# untitled.net
KiCad netlist of a schematic drawn in EAGLE
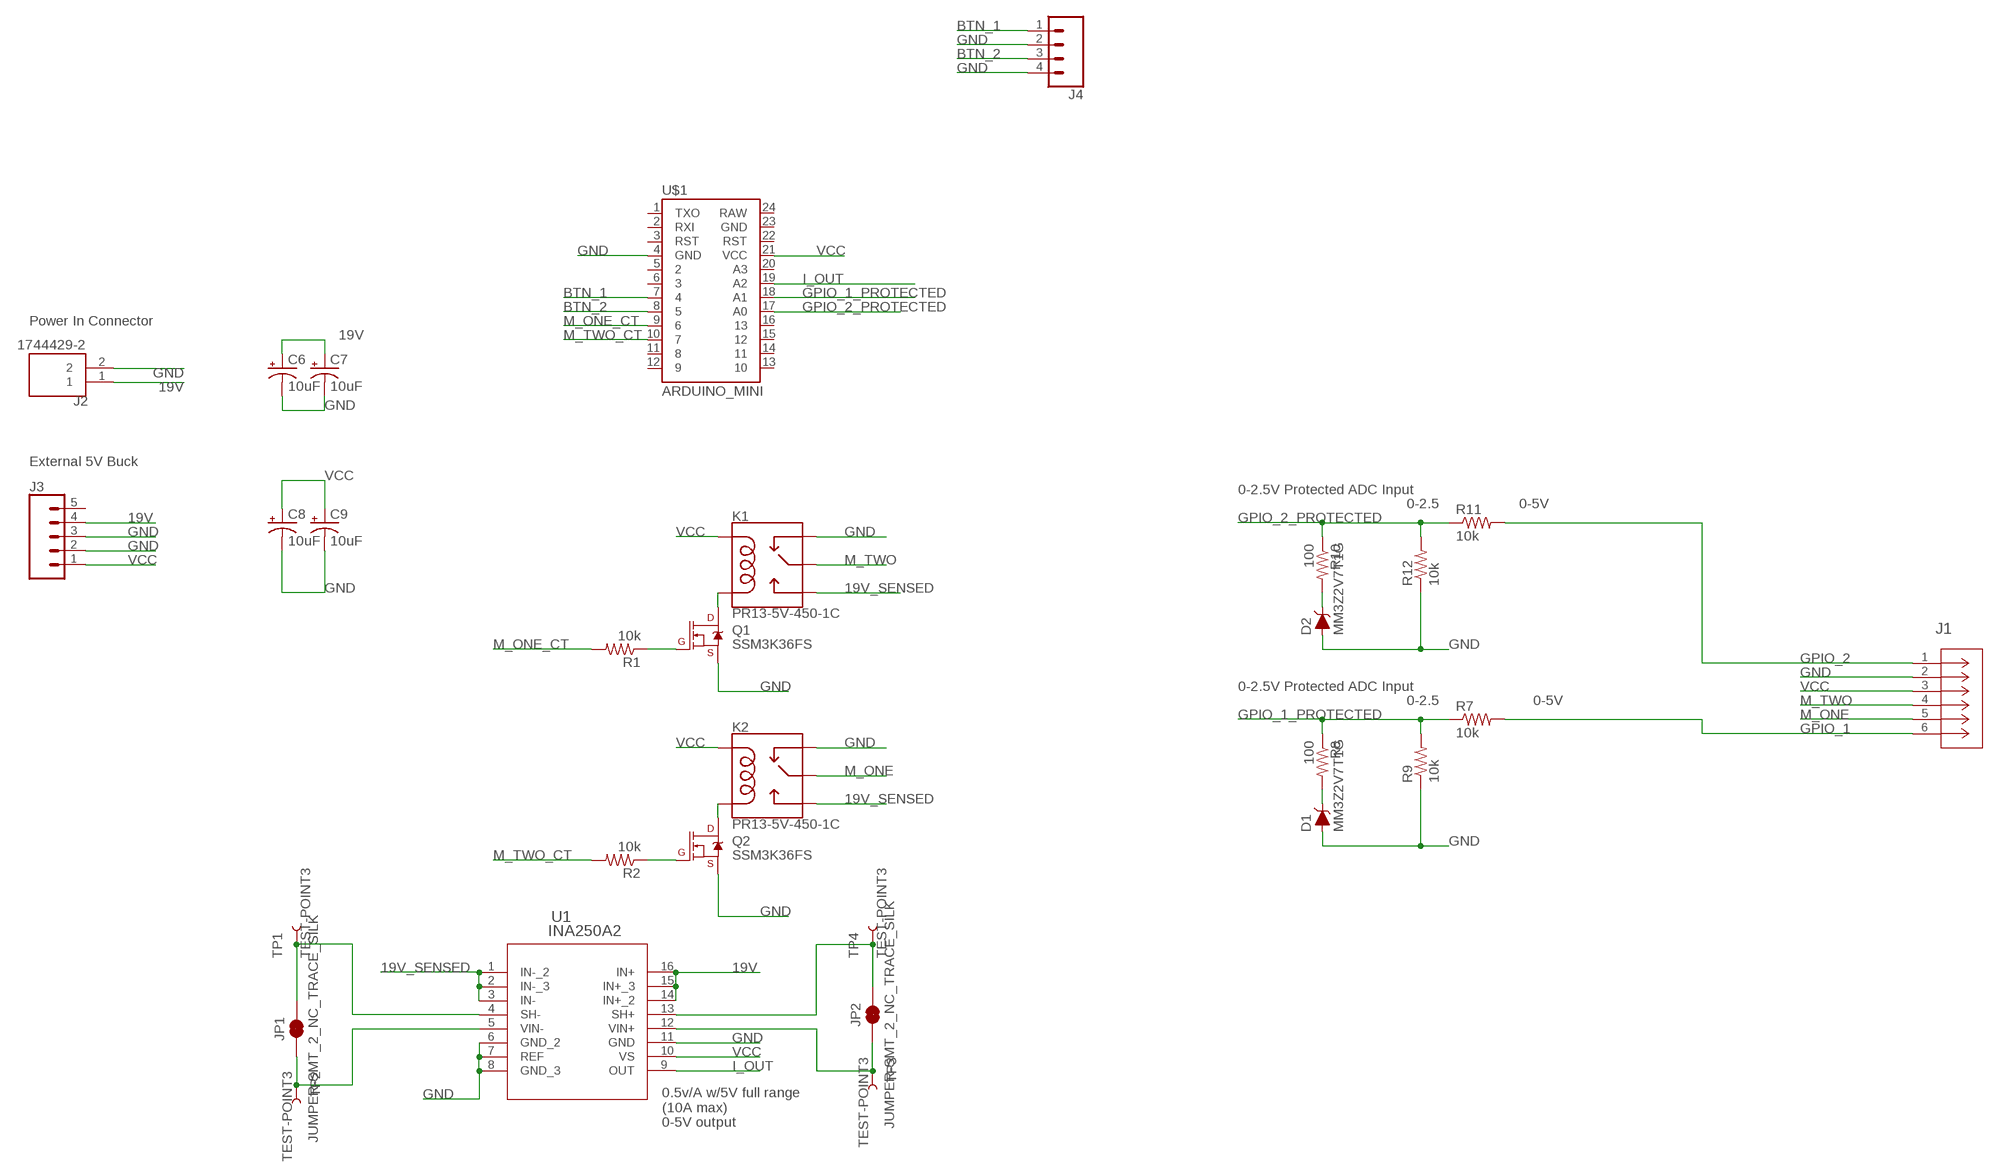
[diagram p0: schematic, sheet 1]

(export (version "E")
  (design (tool "Eeschema 10.0.6"))
  (components
    (comp (ref "C6")
      (value "10uF")
      (footprint "eagle-import:E2,5-6")
      (libsource (lib "eagle-import") (part "CPOL-USE2.5-6"))
    )
    (comp (ref "C7")
      (value "10uF")
      (footprint "eagle-import:E2,5-6")
      (libsource (lib "eagle-import") (part "CPOL-USE2.5-6"))
    )
    (comp (ref "C8")
      (value "10uF")
      (footprint "eagle-import:E2,5-6")
      (libsource (lib "eagle-import") (part "CPOL-USE2.5-6"))
    )
    (comp (ref "C9")
      (value "10uF")
      (footprint "eagle-import:E2,5-6")
      (libsource (lib "eagle-import") (part "CPOL-USE2.5-6"))
    )
    (comp (ref "D1")
      (value "MM3Z2V7T1G")
      (footprint "eagle-import:SOD-323")
      (libsource (lib "eagle-import") (part "DIODE-ZENER-BZT52C3V6S"))
    )
    (comp (ref "D2")
      (value "MM3Z2V7T1G")
      (footprint "eagle-import:SOD-323")
      (libsource (lib "eagle-import") (part "DIODE-ZENER-BZT52C3V6S"))
    )
    (comp (ref "J1")
      (value "39301060")
      (footprint "eagle-import:CON_39301060")
      (fields (field (name "COPYRIGHT") "Copyright (C) 2022 Ultra Librarian. All rights reserved."))
      (libsource (lib "eagle-import") (part "39301060"))
    )
    (comp (ref "J2")
      (value "1744429-2")
      (footprint "eagle-import:TE_1744429-2")
      (fields (field (name "MANUFACTURER") "TE"))
      (libsource (lib "eagle-import") (part "1744429-2"))
    )
    (comp (ref "J3")
      (value "CONN_05")
      (footprint "eagle-import:1X05")
      (libsource (lib "eagle-import") (part "CONN_05"))
    )
    (comp (ref "J4")
      (value "CONN_041X04_NO_SILK")
      (footprint "eagle-import:1X04_NO_SILK")
      (libsource (lib "eagle-import") (part "CONN_041X04_NO_SILK"))
    )
    (comp (ref "JP1")
      (value "JUMPER-SMT_2_NC_TRACE_SILK")
      (footprint "eagle-import:SMT-JUMPER_2_NC_TRACE_SILK")
      (libsource (lib "eagle-import") (part "JUMPER-SMT_2_NC_TRACE_SILK"))
    )
    (comp (ref "JP2")
      (value "JUMPER-SMT_2_NC_TRACE_SILK")
      (footprint "eagle-import:SMT-JUMPER_2_NC_TRACE_SILK")
      (libsource (lib "eagle-import") (part "JUMPER-SMT_2_NC_TRACE_SILK"))
    )
    (comp (ref "K1")
      (value "PR13-5V-450-1C")
      (footprint "eagle-import:RELAY_G5LE")
      (libsource (lib "eagle-import") (part "RELAY-SPDT"))
    )
    (comp (ref "K2")
      (value "PR13-5V-450-1C")
      (footprint "eagle-import:RELAY_G5LE")
      (libsource (lib "eagle-import") (part "RELAY-SPDT"))
    )
    (comp (ref "Q1")
      (value "SSM3K36FS")
      (footprint "eagle-import:SOT23-3")
      (libsource (lib "eagle-import") (part "MOSFET-NCH-AO3404A"))
    )
    (comp (ref "Q2")
      (value "SSM3K36FS")
      (footprint "eagle-import:SOT23-3")
      (libsource (lib "eagle-import") (part "MOSFET-NCH-AO3404A"))
    )
    (comp (ref "R1")
      (value "10k")
      (footprint "eagle-import:R0805")
      (libsource (lib "eagle-import") (part "R-US_R0805"))
    )
    (comp (ref "R2")
      (value "10k")
      (footprint "eagle-import:R0805")
      (libsource (lib "eagle-import") (part "R-US_R0805"))
    )
    (comp (ref "R7")
      (value "10k")
      (footprint "eagle-import:R0805")
      (libsource (lib "eagle-import") (part "R-US_R0805"))
    )
    (comp (ref "R8")
      (value "100")
      (footprint "eagle-import:R0805")
      (libsource (lib "eagle-import") (part "R-US_R0805"))
    )
    (comp (ref "R9")
      (value "10k")
      (footprint "eagle-import:R0805")
      (libsource (lib "eagle-import") (part "R-US_R0805"))
    )
    (comp (ref "R10")
      (value "100")
      (footprint "eagle-import:R0805")
      (libsource (lib "eagle-import") (part "R-US_R0805"))
    )
    (comp (ref "R11")
      (value "10k")
      (footprint "eagle-import:R0805")
      (libsource (lib "eagle-import") (part "R-US_R0805"))
    )
    (comp (ref "R12")
      (value "10k")
      (footprint "eagle-import:R0805")
      (libsource (lib "eagle-import") (part "R-US_R0805"))
    )
    (comp (ref "TP1")
      (value "TEST-POINT3")
      (footprint "eagle-import:PAD.03X.03")
      (libsource (lib "eagle-import") (part "TEST-POINT3"))
    )
    (comp (ref "TP2")
      (value "TEST-POINT3")
      (footprint "eagle-import:PAD.03X.03")
      (libsource (lib "eagle-import") (part "TEST-POINT3"))
    )
    (comp (ref "TP3")
      (value "TEST-POINT3")
      (footprint "eagle-import:PAD.03X.03")
      (libsource (lib "eagle-import") (part "TEST-POINT3"))
    )
    (comp (ref "TP4")
      (value "TEST-POINT3")
      (footprint "eagle-import:PAD.03X.03")
      (libsource (lib "eagle-import") (part "TEST-POINT3"))
    )
    (comp (ref "U$1")
      (value "ARDUINO_MINI")
      (footprint "eagle-import:ARDUINO_MINI")
      (libsource (lib "eagle-import") (part "ARDUINO_MINI"))
    )
    (comp (ref "U1")
      (value "INA250A2")
      (footprint "eagle-import:PW16_TEX-M")
      (fields
        (field (name "MANUFACTURER_PART_NUMBER") "INA250A1PW")
        (field (name "COPYRIGHT") "Copyright (C) 2022 Ultra Librarian. All rights reserved.")
      )
      (libsource (lib "eagle-import") (part "INA250A1PWPW16_TEX-M"))
    )
  )
  (nets
    (net (code "1") (name "/19V") (class "Default")
      (node (ref "C6") (pin "+") (pinfunction "+_+") (pintype "passive"))
      (node (ref "C7") (pin "+") (pinfunction "+_+") (pintype "passive"))
      (node (ref "J2") (pin "1") (pinfunction "1_1") (pintype "passive"))
      (node (ref "J3") (pin "4") (pinfunction "4_4") (pintype "passive"))
      (node (ref "U1") (pin "14") (pinfunction "IN+_2_14") (pintype "input"))
      (node (ref "U1") (pin "15") (pinfunction "IN+_3_15") (pintype "input"))
      (node (ref "U1") (pin "16") (pinfunction "IN+_16") (pintype "input"))
    )
    (net (code "2") (name "/19V_SENSED") (class "Default")
      (node (ref "K1") (pin "3") (pinfunction "NO_3") (pintype "bidirectional"))
      (node (ref "K2") (pin "3") (pinfunction "NO_3") (pintype "bidirectional"))
      (node (ref "U1") (pin "1") (pinfunction "IN-_2_1") (pintype "input"))
      (node (ref "U1") (pin "2") (pinfunction "IN-_3_2") (pintype "input"))
      (node (ref "U1") (pin "3") (pinfunction "IN-_3") (pintype "input"))
    )
    (net (code "3") (name "/BTN_1") (class "Default")
      (node (ref "J4") (pin "1") (pinfunction "1_1") (pintype "passive"))
      (node (ref "U$1") (pin "7") (pinfunction "4_7") (pintype "bidirectional"))
    )
    (net (code "4") (name "/BTN_2") (class "Default")
      (node (ref "J4") (pin "3") (pinfunction "3_3") (pintype "passive"))
      (node (ref "U$1") (pin "8") (pinfunction "5_8") (pintype "bidirectional"))
    )
    (net (code "5") (name "/GND") (class "Default")
      (node (ref "C6") (pin "-") (pinfunction "-_-") (pintype "passive"))
      (node (ref "C7") (pin "-") (pinfunction "-_-") (pintype "passive"))
      (node (ref "C8") (pin "-") (pinfunction "-_-") (pintype "passive"))
      (node (ref "C9") (pin "-") (pinfunction "-_-") (pintype "passive"))
      (node (ref "D1") (pin "A") (pinfunction "A_A") (pintype "passive"))
      (node (ref "D2") (pin "A") (pinfunction "A_A") (pintype "passive"))
      (node (ref "J1") (pin "2") (pinfunction "2_2") (pintype "passive"))
      (node (ref "J2") (pin "2") (pinfunction "2_2") (pintype "passive"))
      (node (ref "J3") (pin "2") (pinfunction "2_2") (pintype "passive"))
      (node (ref "J3") (pin "3") (pinfunction "3_3") (pintype "passive"))
      (node (ref "J4") (pin "2") (pinfunction "2_2") (pintype "passive"))
      (node (ref "J4") (pin "4") (pinfunction "4_4") (pintype "passive"))
      (node (ref "K1") (pin "4") (pinfunction "NC_4") (pintype "bidirectional"))
      (node (ref "K2") (pin "4") (pinfunction "NC_4") (pintype "bidirectional"))
      (node (ref "Q1") (pin "2") (pinfunction "S_2") (pintype "bidirectional"))
      (node (ref "Q2") (pin "2") (pinfunction "S_2") (pintype "bidirectional"))
      (node (ref "R12") (pin "1") (pinfunction "1_1") (pintype "passive"))
      (node (ref "R9") (pin "1") (pinfunction "1_1") (pintype "passive"))
      (node (ref "U$1") (pin "4") (pinfunction "GND_4") (pintype "bidirectional"))
      (node (ref "U1") (pin "11") (pinfunction "GND_11") (pintype "power_in"))
      (node (ref "U1") (pin "6") (pinfunction "GND_2_6") (pintype "power_in"))
      (node (ref "U1") (pin "7") (pinfunction "REF_7") (pintype "input"))
      (node (ref "U1") (pin "8") (pinfunction "GND_3_8") (pintype "power_in"))
    )
    (net (code "6") (name "/GPIO_1") (class "Default")
      (node (ref "J1") (pin "6") (pinfunction "6_6") (pintype "passive"))
      (node (ref "R7") (pin "2") (pinfunction "2_2") (pintype "passive"))
    )
    (net (code "7") (name "/GPIO_1_PROTECTED") (class "Default")
      (node (ref "R7") (pin "1") (pinfunction "1_1") (pintype "passive"))
      (node (ref "R8") (pin "1") (pinfunction "1_1") (pintype "passive"))
      (node (ref "R9") (pin "2") (pinfunction "2_2") (pintype "passive"))
      (node (ref "U$1") (pin "18") (pinfunction "A1_18") (pintype "bidirectional"))
    )
    (net (code "8") (name "/GPIO_2") (class "Default")
      (node (ref "J1") (pin "1") (pinfunction "1_1") (pintype "passive"))
      (node (ref "R11") (pin "2") (pinfunction "2_2") (pintype "passive"))
    )
    (net (code "9") (name "/GPIO_2_PROTECTED") (class "Default")
      (node (ref "R10") (pin "1") (pinfunction "1_1") (pintype "passive"))
      (node (ref "R11") (pin "1") (pinfunction "1_1") (pintype "passive"))
      (node (ref "R12") (pin "2") (pinfunction "2_2") (pintype "passive"))
      (node (ref "U$1") (pin "17") (pinfunction "A0_17") (pintype "bidirectional"))
    )
    (net (code "10") (name "/I_OUT") (class "Default")
      (node (ref "U$1") (pin "19") (pinfunction "A2_19") (pintype "bidirectional"))
      (node (ref "U1") (pin "9") (pinfunction "OUT_9") (pintype "output"))
    )
    (net (code "11") (name "/M_ONE") (class "Default")
      (node (ref "J1") (pin "5") (pinfunction "5_5") (pintype "passive"))
      (node (ref "K2") (pin "1") (pinfunction "MAIN_1") (pintype "bidirectional"))
    )
    (net (code "12") (name "/M_ONE_CT") (class "Default")
      (node (ref "R1") (pin "2") (pinfunction "2_2") (pintype "passive"))
      (node (ref "U$1") (pin "9") (pinfunction "6_9") (pintype "bidirectional"))
    )
    (net (code "13") (name "/M_TWO") (class "Default")
      (node (ref "J1") (pin "4") (pinfunction "4_4") (pintype "passive"))
      (node (ref "K1") (pin "1") (pinfunction "MAIN_1") (pintype "bidirectional"))
    )
    (net (code "14") (name "/M_TWO_CT") (class "Default")
      (node (ref "R2") (pin "2") (pinfunction "2_2") (pintype "passive"))
      (node (ref "U$1") (pin "10") (pinfunction "7_10") (pintype "bidirectional"))
    )
    (net (code "15") (name "/VCC") (class "Default")
      (node (ref "C8") (pin "+") (pinfunction "+_+") (pintype "passive"))
      (node (ref "C9") (pin "+") (pinfunction "+_+") (pintype "passive"))
      (node (ref "J1") (pin "3") (pinfunction "3_3") (pintype "passive"))
      (node (ref "J3") (pin "1") (pinfunction "1_1") (pintype "passive"))
      (node (ref "K1") (pin "2") (pinfunction "COIL1_2") (pintype "bidirectional"))
      (node (ref "K2") (pin "2") (pinfunction "COIL1_2") (pintype "bidirectional"))
      (node (ref "U$1") (pin "21") (pinfunction "VCC_21") (pintype "bidirectional"))
      (node (ref "U1") (pin "10") (pinfunction "VS_10") (pintype "power_in"))
    )
    (net (code "16") (name "Net-(D1-PadC)") (class "Default")
      (node (ref "D1") (pin "C") (pinfunction "C_C") (pintype "passive"))
      (node (ref "R8") (pin "2") (pinfunction "2_2") (pintype "passive"))
    )
    (net (code "17") (name "Net-(D2-PadC)") (class "Default")
      (node (ref "D2") (pin "C") (pinfunction "C_C") (pintype "passive"))
      (node (ref "R10") (pin "2") (pinfunction "2_2") (pintype "passive"))
    )
    (net (code "18") (name "Net-(K1-COIL2)") (class "Default")
      (node (ref "K1") (pin "5") (pinfunction "COIL2_5") (pintype "bidirectional"))
      (node (ref "Q1") (pin "3") (pinfunction "D_3") (pintype "bidirectional"))
    )
    (net (code "19") (name "Net-(K2-COIL2)") (class "Default")
      (node (ref "K2") (pin "5") (pinfunction "COIL2_5") (pintype "bidirectional"))
      (node (ref "Q2") (pin "3") (pinfunction "D_3") (pintype "bidirectional"))
    )
    (net (code "20") (name "Net-(Q1-G)") (class "Default")
      (node (ref "Q1") (pin "1") (pinfunction "G_1") (pintype "bidirectional"))
      (node (ref "R1") (pin "1") (pinfunction "1_1") (pintype "passive"))
    )
    (net (code "21") (name "Net-(Q2-G)") (class "Default")
      (node (ref "Q2") (pin "1") (pinfunction "G_1") (pintype "bidirectional"))
      (node (ref "R2") (pin "1") (pinfunction "1_1") (pintype "passive"))
    )
    (net (code "22") (name "Net-(U1-SH+)") (class "Default")
      (node (ref "JP2") (pin "2") (pinfunction "2_2") (pintype "passive"))
      (node (ref "TP4") (pin "1") (pinfunction "1_1") (pintype "bidirectional"))
      (node (ref "U1") (pin "13") (pinfunction "SH+_13") (pintype "output"))
    )
    (net (code "23") (name "Net-(U1-SH-)") (class "Default")
      (node (ref "JP1") (pin "2") (pinfunction "2_2") (pintype "passive"))
      (node (ref "TP1") (pin "1") (pinfunction "1_1") (pintype "bidirectional"))
      (node (ref "U1") (pin "4") (pinfunction "SH-_4") (pintype "output"))
    )
    (net (code "24") (name "Net-(U1-VIN+)") (class "Default")
      (node (ref "JP2") (pin "1") (pinfunction "1_1") (pintype "passive"))
      (node (ref "TP3") (pin "1") (pinfunction "1_1") (pintype "bidirectional"))
      (node (ref "U1") (pin "12") (pinfunction "VIN+_12") (pintype "input"))
    )
    (net (code "25") (name "Net-(U1-VIN-)") (class "Default")
      (node (ref "JP1") (pin "1") (pinfunction "1_1") (pintype "passive"))
      (node (ref "TP2") (pin "1") (pinfunction "1_1") (pintype "bidirectional"))
      (node (ref "U1") (pin "5") (pinfunction "VIN-_5") (pintype "input"))
    )
    (net (code "26") (name "unconnected-(J3-Pad5)") (class "Default")
      (node (ref "J3") (pin "5") (pinfunction "5_5") (pintype "passive"))
    )
    (net (code "27") (name "unconnected-(U$1-2-Pad5)") (class "Default")
      (node (ref "U$1") (pin "5") (pinfunction "2_5") (pintype "bidirectional"))
    )
    (net (code "28") (name "unconnected-(U$1-3-Pad6)") (class "Default")
      (node (ref "U$1") (pin "6") (pinfunction "3_6") (pintype "bidirectional"))
    )
    (net (code "29") (name "unconnected-(U$1-8-Pad11)") (class "Default")
      (node (ref "U$1") (pin "11") (pinfunction "8_11") (pintype "bidirectional"))
    )
    (net (code "30") (name "unconnected-(U$1-9-Pad12)") (class "Default")
      (node (ref "U$1") (pin "12") (pinfunction "9_12") (pintype "bidirectional"))
    )
    (net (code "31") (name "unconnected-(U$1-10-Pad13)") (class "Default")
      (node (ref "U$1") (pin "13") (pinfunction "10_13") (pintype "bidirectional"))
    )
    (net (code "32") (name "unconnected-(U$1-11-Pad14)") (class "Default")
      (node (ref "U$1") (pin "14") (pinfunction "11_14") (pintype "bidirectional"))
    )
    (net (code "33") (name "unconnected-(U$1-12-Pad15)") (class "Default")
      (node (ref "U$1") (pin "15") (pinfunction "12_15") (pintype "bidirectional"))
    )
    (net (code "34") (name "unconnected-(U$1-13-Pad16)") (class "Default")
      (node (ref "U$1") (pin "16") (pinfunction "13_16") (pintype "bidirectional"))
    )
    (net (code "35") (name "unconnected-(U$1-A3-Pad20)") (class "Default")
      (node (ref "U$1") (pin "20") (pinfunction "A3_20") (pintype "bidirectional"))
    )
    (net (code "36") (name "unconnected-(U$1-GND-Pad23)") (class "Default")
      (node (ref "U$1") (pin "23") (pinfunction "GND_23") (pintype "bidirectional"))
    )
    (net (code "37") (name "unconnected-(U$1-RAW-Pad24)") (class "Default")
      (node (ref "U$1") (pin "24") (pinfunction "RAW_24") (pintype "bidirectional"))
    )
    (net (code "38") (name "unconnected-(U$1-RST-Pad3)") (class "Default")
      (node (ref "U$1") (pin "3") (pinfunction "RST_3") (pintype "bidirectional"))
    )
    (net (code "39") (name "unconnected-(U$1-RST-Pad22)") (class "Default")
      (node (ref "U$1") (pin "22") (pinfunction "RST_22") (pintype "bidirectional"))
    )
    (net (code "40") (name "unconnected-(U$1-RXI-Pad2)") (class "Default")
      (node (ref "U$1") (pin "2") (pinfunction "RXI_2") (pintype "bidirectional"))
    )
    (net (code "41") (name "unconnected-(U$1-TXO-Pad1)") (class "Default")
      (node (ref "U$1") (pin "1") (pinfunction "TXO_1") (pintype "bidirectional"))
    )
  )
)
